# LcsNodes-Extension-Servo-Board-32-S-B_01.net
KiCad netlist of a schematic drawn in EasyEDA
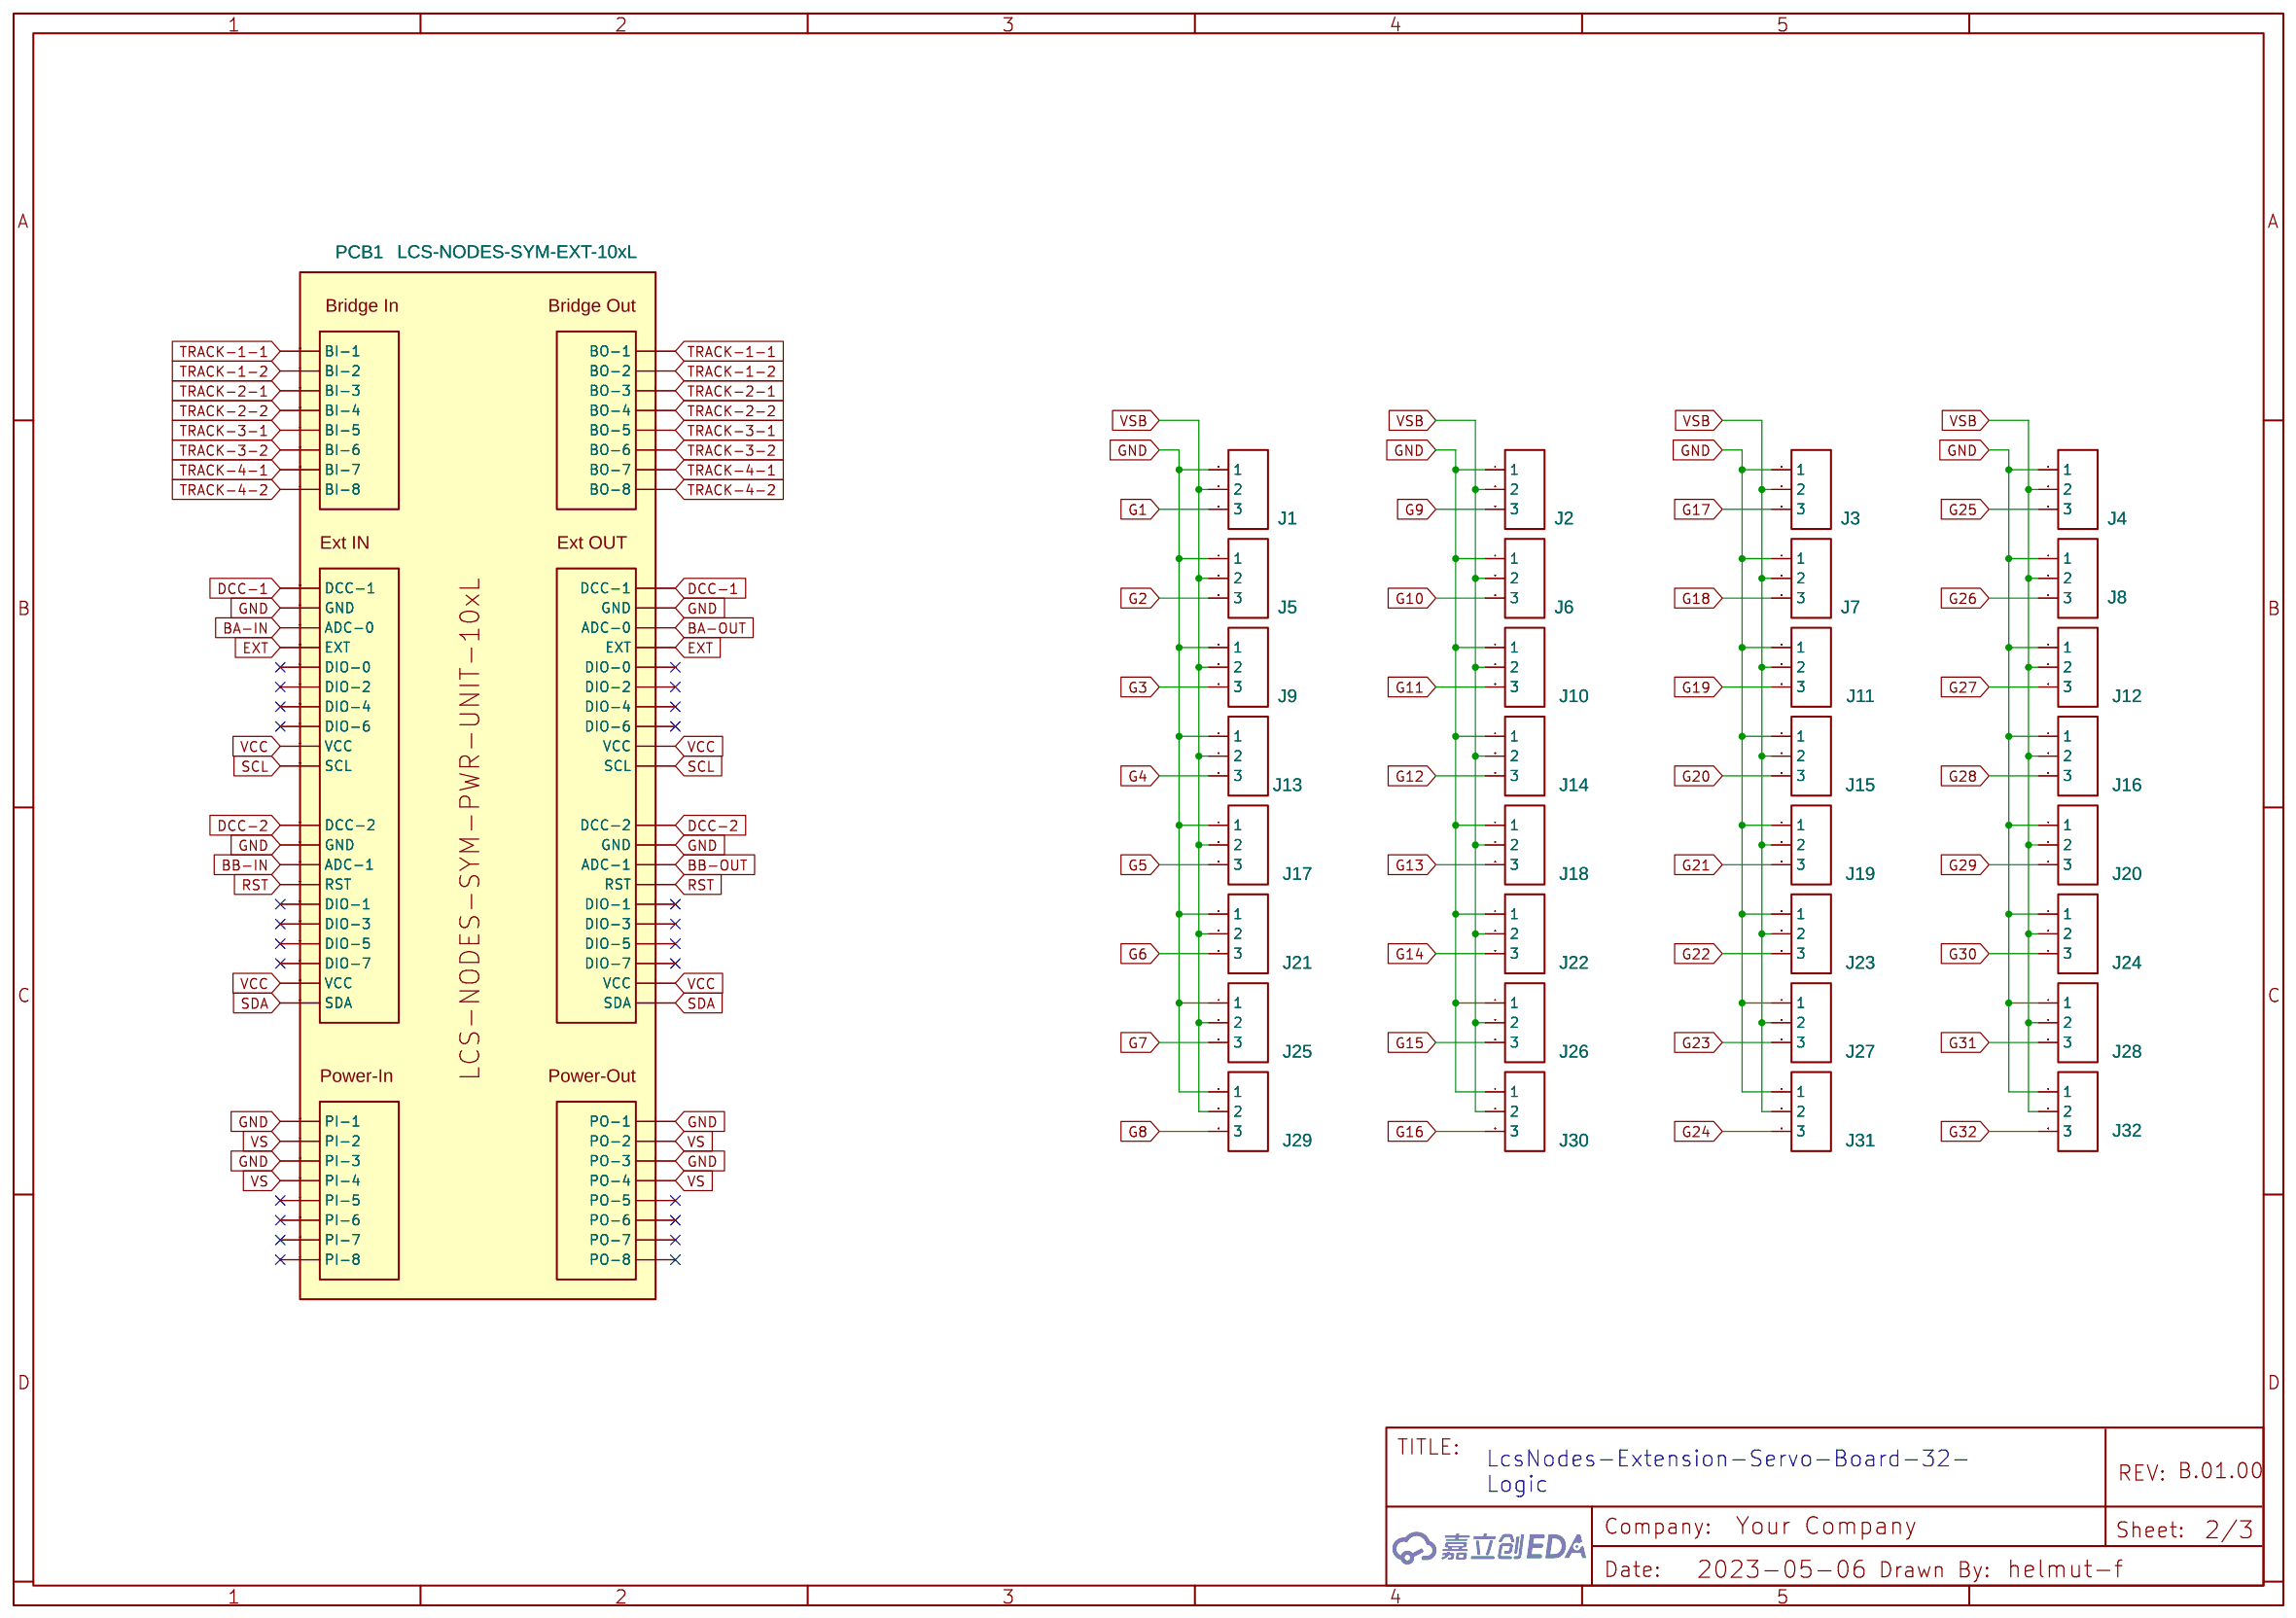
[diagram p0: Connectors]
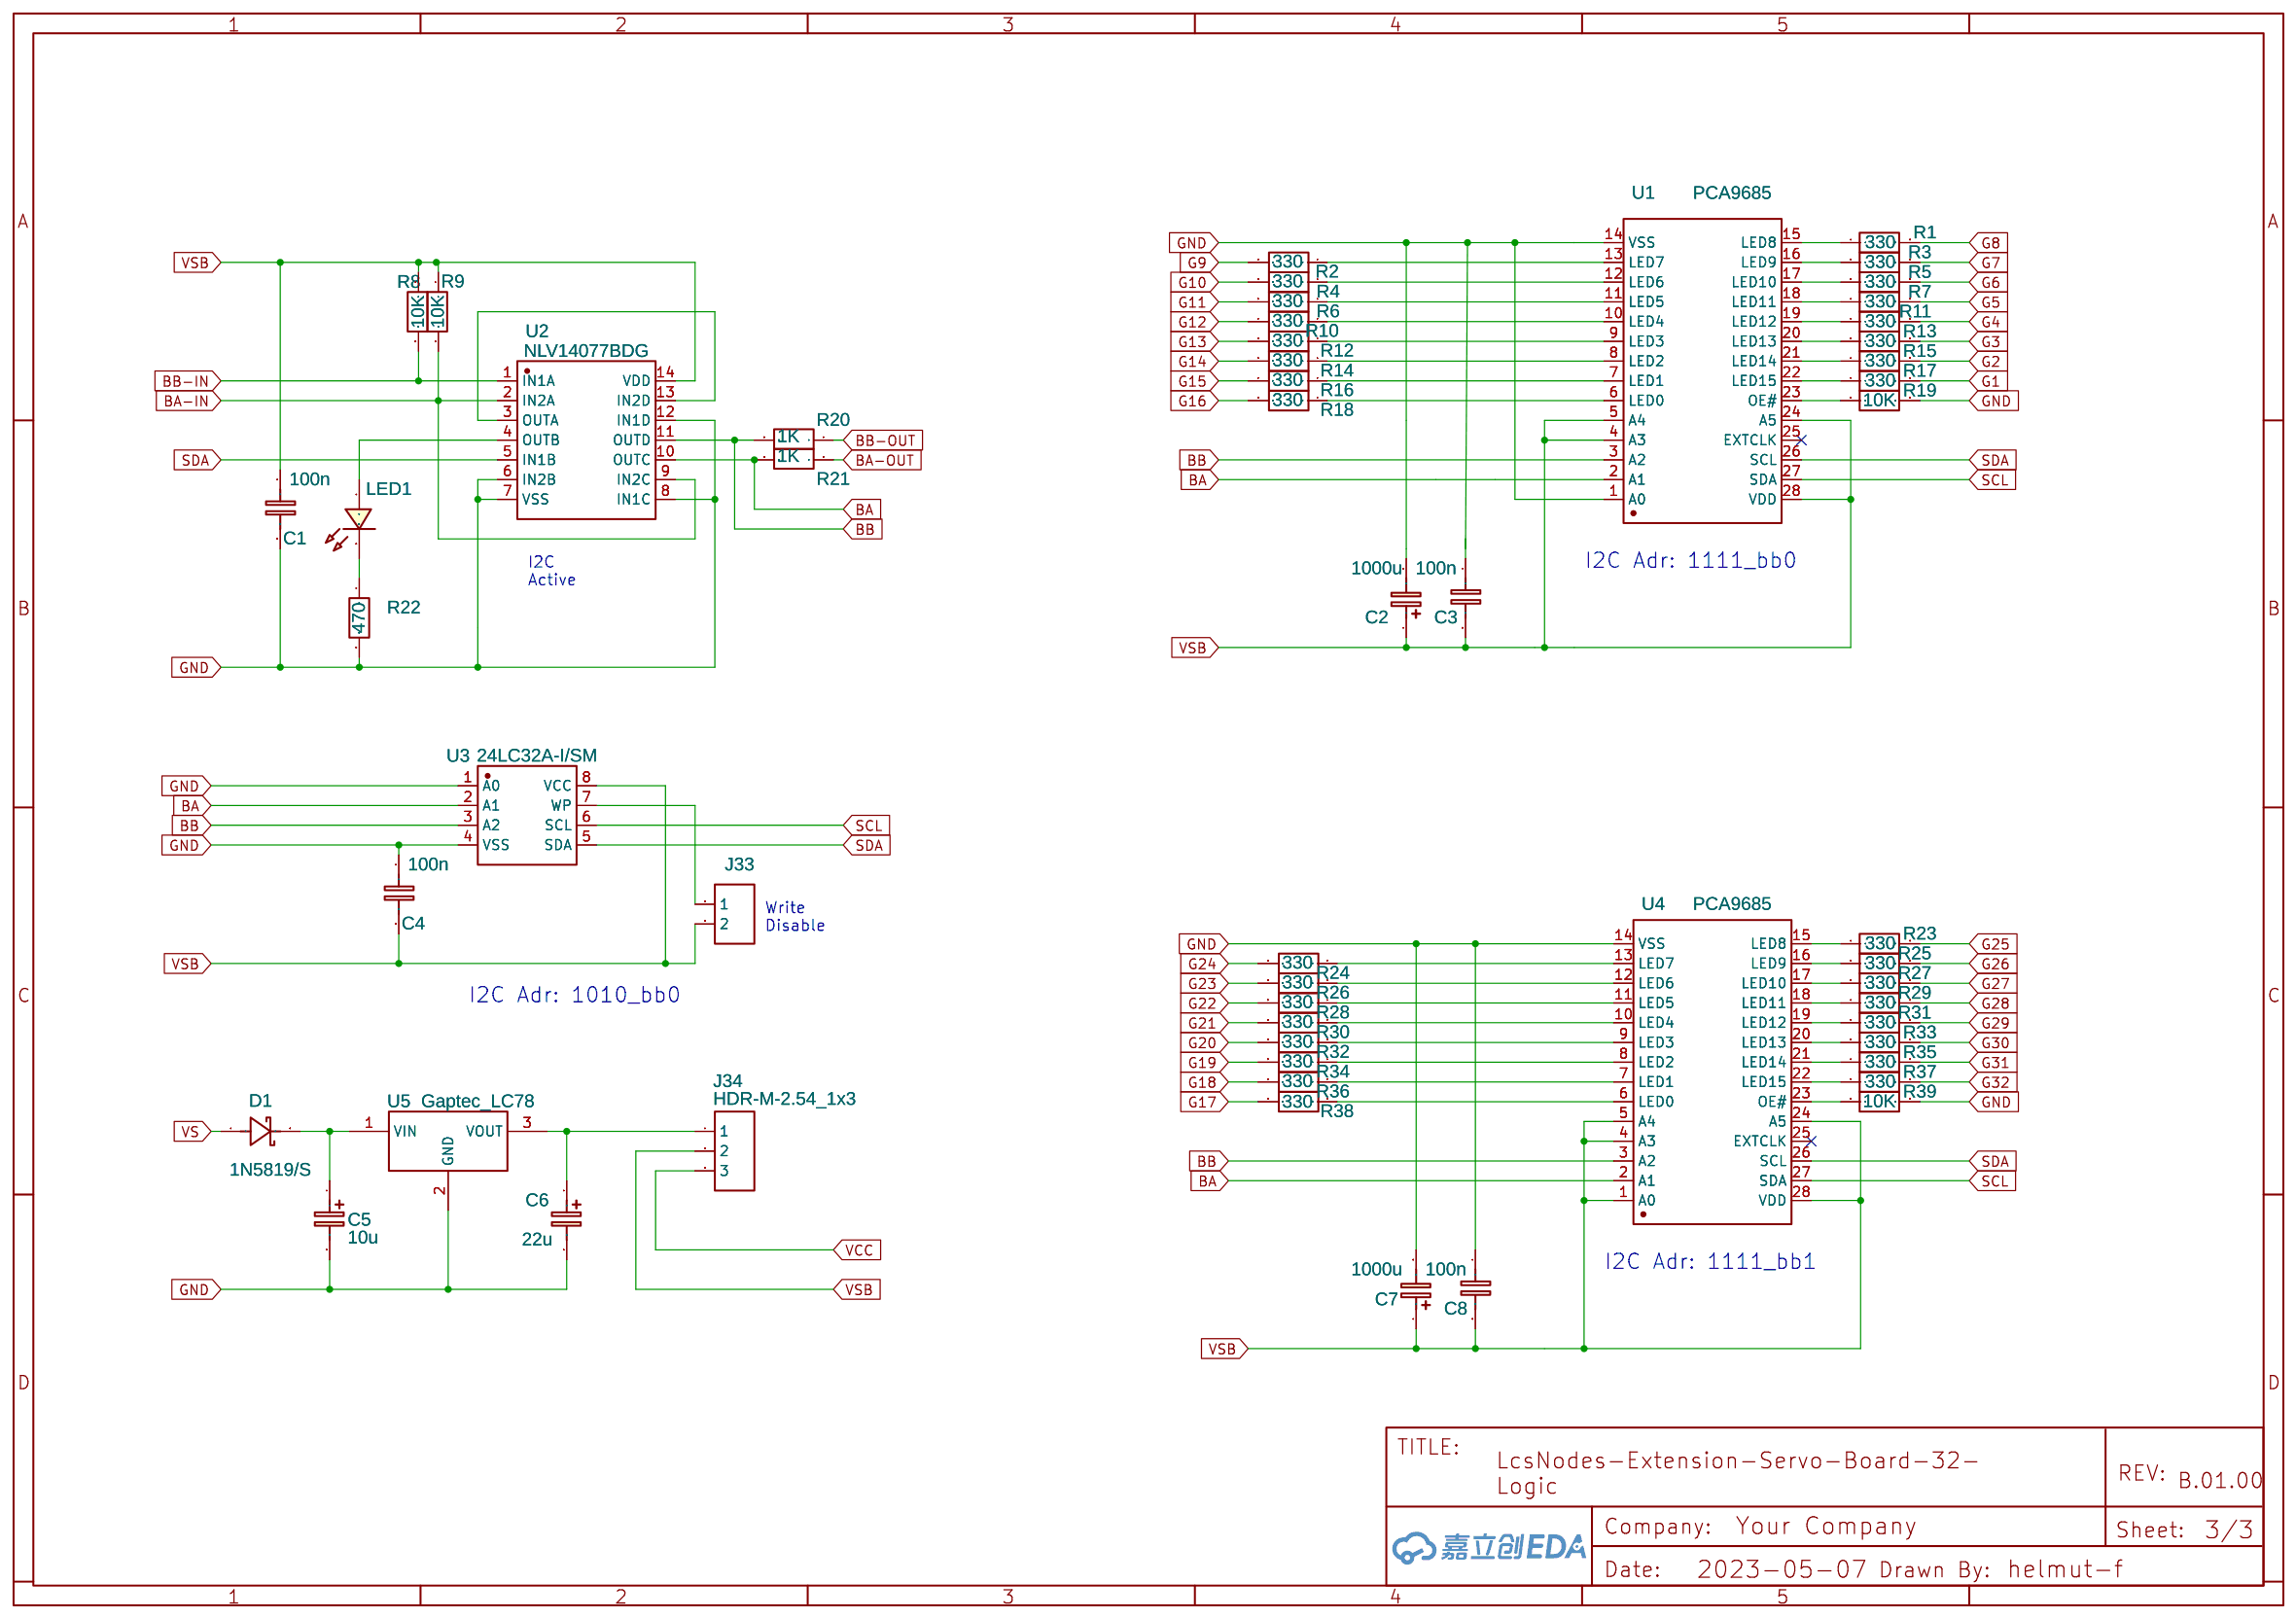
[diagram p1: Logic]
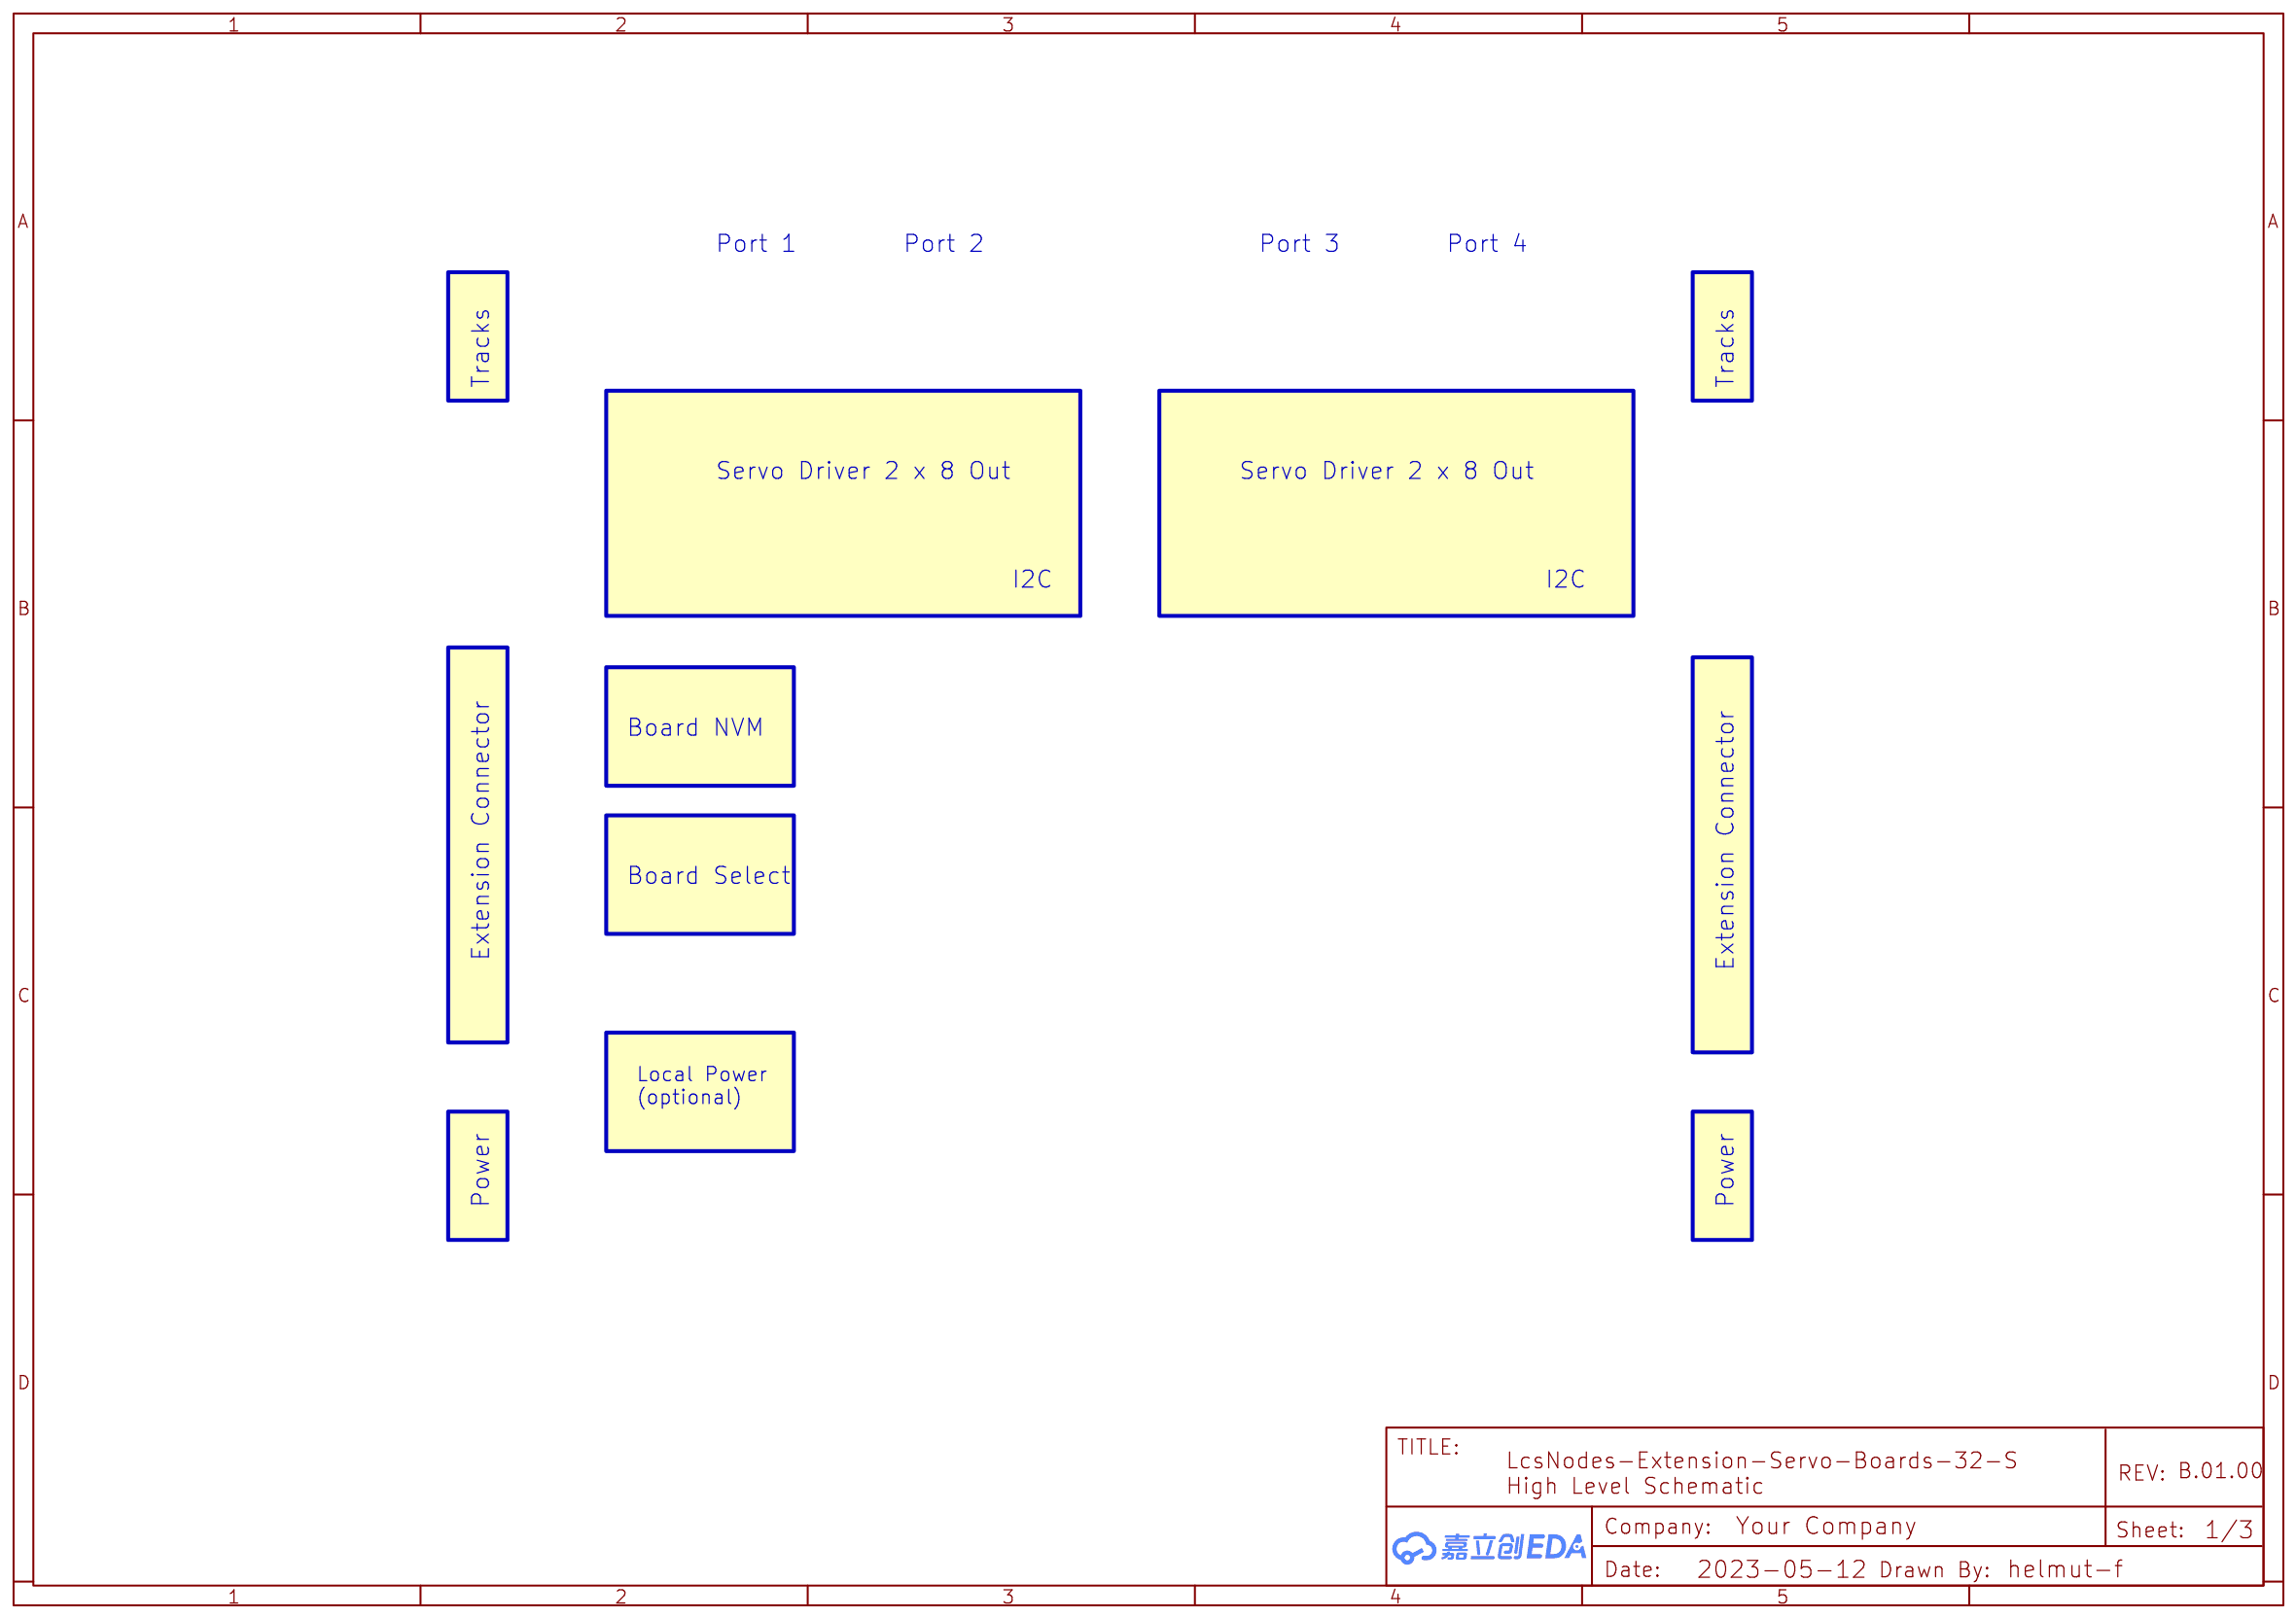
[diagram p2: High Level Schematic]

(export (version "E")
  (design (tool "Eeschema 10.0.6"))
  (components
    (comp (ref "J1") (value "HDR-M-2.54_1x3") (libsource (lib "") (part "HDR-M-2.54_1x3")))
    (comp (ref "J2") (value "HDR-M-2.54_1x3") (libsource (lib "") (part "HDR-M-2.54_1x3")))
    (comp (ref "J3") (value "HDR-M-2.54_1x3") (libsource (lib "") (part "HDR-M-2.54_1x3")))
    (comp (ref "J4") (value "HDR-M-2.54_1x3") (libsource (lib "") (part "HDR-M-2.54_1x3")))
    (comp (ref "J5") (value "HDR-M-2.54_1x3") (libsource (lib "") (part "HDR-M-2.54_1x3")))
    (comp (ref "J6") (value "HDR-M-2.54_1x3") (libsource (lib "") (part "HDR-M-2.54_1x3")))
    (comp (ref "J7") (value "HDR-M-2.54_1x3") (libsource (lib "") (part "HDR-M-2.54_1x3")))
    (comp (ref "J8") (value "HDR-M-2.54_1x3") (libsource (lib "") (part "HDR-M-2.54_1x3")))
    (comp (ref "J9") (value "HDR-M-2.54_1x3") (libsource (lib "") (part "HDR-M-2.54_1x3")))
    (comp (ref "J10") (value "HDR-M-2.54_1x3") (libsource (lib "") (part "HDR-M-2.54_1x3")))
    (comp (ref "J11") (value "HDR-M-2.54_1x3") (libsource (lib "") (part "HDR-M-2.54_1x3")))
    (comp (ref "J12") (value "HDR-M-2.54_1x3") (libsource (lib "") (part "HDR-M-2.54_1x3")))
    (comp (ref "J13") (value "HDR-M-2.54_1x3") (libsource (lib "") (part "HDR-M-2.54_1x3")))
    (comp (ref "J14") (value "HDR-M-2.54_1x3") (libsource (lib "") (part "HDR-M-2.54_1x3")))
    (comp (ref "J15") (value "HDR-M-2.54_1x3") (libsource (lib "") (part "HDR-M-2.54_1x3")))
    (comp (ref "J16") (value "HDR-M-2.54_1x3") (libsource (lib "") (part "HDR-M-2.54_1x3")))
    (comp (ref "J17") (value "HDR-M-2.54_1x3") (libsource (lib "") (part "HDR-M-2.54_1x3")))
    (comp (ref "J18") (value "HDR-M-2.54_1x3") (libsource (lib "") (part "HDR-M-2.54_1x3")))
    (comp (ref "J19") (value "HDR-M-2.54_1x3") (libsource (lib "") (part "HDR-M-2.54_1x3")))
    (comp (ref "J20") (value "HDR-M-2.54_1x3") (libsource (lib "") (part "HDR-M-2.54_1x3")))
    (comp (ref "J21") (value "HDR-M-2.54_1x3") (libsource (lib "") (part "HDR-M-2.54_1x3")))
    (comp (ref "J22") (value "HDR-M-2.54_1x3") (libsource (lib "") (part "HDR-M-2.54_1x3")))
    (comp (ref "J23") (value "HDR-M-2.54_1x3") (libsource (lib "") (part "HDR-M-2.54_1x3")))
    (comp (ref "J24") (value "HDR-M-2.54_1x3") (libsource (lib "") (part "HDR-M-2.54_1x3")))
    (comp (ref "J25") (value "HDR-M-2.54_1x3") (libsource (lib "") (part "HDR-M-2.54_1x3")))
    (comp (ref "J26") (value "HDR-M-2.54_1x3") (libsource (lib "") (part "HDR-M-2.54_1x3")))
    (comp (ref "J27") (value "HDR-M-2.54_1x3") (libsource (lib "") (part "HDR-M-2.54_1x3")))
    (comp (ref "J28") (value "HDR-M-2.54_1x3") (libsource (lib "") (part "HDR-M-2.54_1x3")))
    (comp (ref "J29") (value "HDR-M-2.54_1x3") (libsource (lib "") (part "HDR-M-2.54_1x3")))
    (comp (ref "J30") (value "HDR-M-2.54_1x3") (libsource (lib "") (part "HDR-M-2.54_1x3")))
    (comp (ref "J31") (value "HDR-M-2.54_1x3") (libsource (lib "") (part "HDR-M-2.54_1x3")))
    (comp (ref "J32") (value "HDR-M-2.54_1x3") (libsource (lib "") (part "HDR-M-2.54_1x3")))
    (comp (ref "PCB1") (value "LCS-NODES-SYM-EXT-10xL") (libsource (lib "") (part "LCS-NODES-SYM-EXT-10xL")))
    (comp (ref "C1") (value "100n") (libsource (lib "") (part "C_0603_EU_2")))
    (comp (ref "C2") (value "1000u") (libsource (lib "") (part "CE_TH_D4.0×F1.5_EU_1")))
    (comp (ref "C3") (value "100n") (libsource (lib "") (part "C_0603_EU_3")))
    (comp (ref "C4") (value "100n") (libsource (lib "") (part "C_0603_EU")))
    (comp (ref "C5") (value "10u") (libsource (lib "") (part "CE_SMD_D5.0×H5.5_EU_1")))
    (comp (ref "C6") (value "22u") (libsource (lib "") (part "CE_SMD_D5.0×H5.5_EU")))
    (comp (ref "C7") (value "1000u") (libsource (lib "") (part "CE_TH_D4.0×F1.5_EU")))
    (comp (ref "C8") (value "100n") (libsource (lib "") (part "C_0603_EU_1")))
    (comp (ref "D1") (value "1N5819/S") (libsource (lib "") (part "1N5819/S")))
    (comp (ref "J33") (value "HDR-M-2.54_1x2") (libsource (lib "") (part "HDR-M-2.54_1x2")))
    (comp (ref "J34") (value "HDR-M-2.54_1x3") (libsource (lib "") (part "HDR-M-2.54_1x3")))
    (comp (ref "LED1")
      (value "LED-0805_G")
      (fields (field (name "Manufacturer Part") "NCD0805G1") (field (name "Manufacturer") "国星光电"))
      (libsource (lib "") (part "LED-0805_G"))
    )
    (comp (ref "R1") (value "330") (libsource (lib "") (part "R_AXIAL-0.3_EU")))
    (comp (ref "R2") (value "330") (libsource (lib "") (part "R_AXIAL-0.3_EU_1")))
    (comp (ref "R3") (value "330") (libsource (lib "") (part "R_AXIAL-0.3_EU")))
    (comp (ref "R4") (value "330") (libsource (lib "") (part "R_AXIAL-0.3_EU_1")))
    (comp (ref "R5") (value "330") (libsource (lib "") (part "R_AXIAL-0.3_EU")))
    (comp (ref "R6") (value "330") (libsource (lib "") (part "R_AXIAL-0.3_EU_1")))
    (comp (ref "R7") (value "330") (libsource (lib "") (part "R_AXIAL-0.3_EU")))
    (comp (ref "R8") (value "10K") (libsource (lib "") (part "R_AXIAL-0.3_EU_3")))
    (comp (ref "R9") (value "10K") (libsource (lib "") (part "R_AXIAL-0.3_EU_3")))
    (comp (ref "R10") (value "330") (libsource (lib "") (part "R_AXIAL-0.3_EU_1")))
    (comp (ref "R11") (value "330") (libsource (lib "") (part "R_AXIAL-0.3_EU")))
    (comp (ref "R12") (value "330") (libsource (lib "") (part "R_AXIAL-0.3_EU_1")))
    (comp (ref "R13") (value "330") (libsource (lib "") (part "R_AXIAL-0.3_EU")))
    (comp (ref "R14") (value "330") (libsource (lib "") (part "R_AXIAL-0.3_EU_1")))
    (comp (ref "R15") (value "330") (libsource (lib "") (part "R_AXIAL-0.3_EU")))
    (comp (ref "R16") (value "330") (libsource (lib "") (part "R_AXIAL-0.3_EU_1")))
    (comp (ref "R17") (value "330") (libsource (lib "") (part "R_AXIAL-0.3_EU")))
    (comp (ref "R18") (value "330") (libsource (lib "") (part "R_AXIAL-0.3_EU_1")))
    (comp (ref "R19") (value "10K") (libsource (lib "") (part "R_AXIAL-0.3_EU")))
    (comp (ref "R20") (value "1K") (libsource (lib "") (part "R_AXIAL-0.3_EU_2")))
    (comp (ref "R21") (value "1K") (libsource (lib "") (part "R_AXIAL-0.3_EU_2")))
    (comp (ref "R22") (value "470") (libsource (lib "") (part "R_0805_EU")))
    (comp (ref "R23") (value "330") (libsource (lib "") (part "R_AXIAL-0.3_EU")))
    (comp (ref "R24") (value "330") (libsource (lib "") (part "R_AXIAL-0.3_EU_1")))
    (comp (ref "R25") (value "330") (libsource (lib "") (part "R_AXIAL-0.3_EU")))
    (comp (ref "R26") (value "330") (libsource (lib "") (part "R_AXIAL-0.3_EU_1")))
    (comp (ref "R27") (value "330") (libsource (lib "") (part "R_AXIAL-0.3_EU")))
    (comp (ref "R28") (value "330") (libsource (lib "") (part "R_AXIAL-0.3_EU_1")))
    (comp (ref "R29") (value "330") (libsource (lib "") (part "R_AXIAL-0.3_EU")))
    (comp (ref "R30") (value "330") (libsource (lib "") (part "R_AXIAL-0.3_EU_1")))
    (comp (ref "R31") (value "330") (libsource (lib "") (part "R_AXIAL-0.3_EU")))
    (comp (ref "R32") (value "330") (libsource (lib "") (part "R_AXIAL-0.3_EU_1")))
    (comp (ref "R33") (value "330") (libsource (lib "") (part "R_AXIAL-0.3_EU")))
    (comp (ref "R34") (value "330") (libsource (lib "") (part "R_AXIAL-0.3_EU_1")))
    (comp (ref "R35") (value "330") (libsource (lib "") (part "R_AXIAL-0.3_EU")))
    (comp (ref "R36") (value "330") (libsource (lib "") (part "R_AXIAL-0.3_EU_1")))
    (comp (ref "R37") (value "330") (libsource (lib "") (part "R_AXIAL-0.3_EU")))
    (comp (ref "R38") (value "330") (libsource (lib "") (part "R_AXIAL-0.3_EU_1")))
    (comp (ref "R39") (value "10K") (libsource (lib "") (part "R_AXIAL-0.3_EU")))
    (comp (ref "U1")
      (value "PCA9685")
      (fields (field (name "Manufacturer Part") "PCA9685PW/Q900,118") (field (name "Manufacturer") "NXP"))
      (libsource (lib "") (part "PCA9685PW/Q900,118"))
    )
    (comp (ref "U2")
      (value "NLV14077BDG")
      (fields (field (name "Manufacturer") "onsemi(安森美)"))
      (libsource (lib "") (part "NLV14077BDG"))
    )
    (comp (ref "U3")
      (value "24LC32A-I/SM")
      (fields (field (name "Manufacturer") "MICROCHIP(美国微芯)"))
      (libsource (lib "") (part "24LC32A-I/SM"))
    )
    (comp (ref "U4")
      (value "PCA9685")
      (fields (field (name "Manufacturer Part") "PCA9685PW/Q900,118") (field (name "Manufacturer") "NXP"))
      (libsource (lib "") (part "PCA9685PW/Q900,118"))
    )
    (comp (ref "U5") (value "Gaptec_LC78") (libsource (lib "") (part "Gaptec_LC78")))
  )
  (nets
    (net (code "1") (name "BA") (class "Default")
      (node (ref "R21") (pin "2") (pinfunction "2_2") (pintype "unspecified"))
      (node (ref "U1") (pin "2") (pinfunction "A1_2") (pintype "unspecified"))
      (node (ref "U2") (pin "10") (pinfunction "OUTC_10") (pintype "unspecified"))
      (node (ref "U3") (pin "2") (pinfunction "A1_2") (pintype "unspecified"))
      (node (ref "U4") (pin "2") (pinfunction "A1_2") (pintype "unspecified"))
    )
    (net (code "2") (name "BA-IN") (class "Default")
      (node (ref "PCB1") (pin "22") (pinfunction "ADC-0_22") (pintype "unspecified"))
      (node (ref "R9") (pin "2") (pinfunction "2_2") (pintype "unspecified"))
      (node (ref "U2") (pin "2") (pinfunction "IN2A_2") (pintype "unspecified"))
      (node (ref "U2") (pin "9") (pinfunction "IN2C_9") (pintype "unspecified"))
    )
    (net (code "3") (name "BA-OUT") (class "Default")
      (node (ref "PCB1") (pin "62") (pinfunction "ADC-0_62") (pintype "unspecified"))
      (node (ref "R21") (pin "1") (pinfunction "1_1") (pintype "unspecified"))
    )
    (net (code "4") (name "BB") (class "Default")
      (node (ref "R20") (pin "2") (pinfunction "2_2") (pintype "unspecified"))
      (node (ref "U1") (pin "3") (pinfunction "A2_3") (pintype "unspecified"))
      (node (ref "U2") (pin "11") (pinfunction "OUTD_11") (pintype "unspecified"))
      (node (ref "U3") (pin "3") (pinfunction "A2_3") (pintype "unspecified"))
      (node (ref "U4") (pin "3") (pinfunction "A2_3") (pintype "unspecified"))
    )
    (net (code "5") (name "BB-IN") (class "Default")
      (node (ref "PCB1") (pin "32") (pinfunction "ADC-1_32") (pintype "unspecified"))
      (node (ref "R8") (pin "2") (pinfunction "2_2") (pintype "unspecified"))
      (node (ref "U2") (pin "1") (pinfunction "IN1A_1") (pintype "unspecified"))
    )
    (net (code "6") (name "BB-OUT") (class "Default")
      (node (ref "PCB1") (pin "72") (pinfunction "ADC-1_72") (pintype "unspecified"))
      (node (ref "R20") (pin "1") (pinfunction "1_1") (pintype "unspecified"))
    )
    (net (code "7") (name "DCC-1") (class "Default")
      (node (ref "PCB1") (pin "20") (pinfunction "DCC-1_20") (pintype "unspecified"))
      (node (ref "PCB1") (pin "60") (pinfunction "DCC-1_60") (pintype "unspecified"))
    )
    (net (code "8") (name "DCC-2") (class "Default")
      (node (ref "PCB1") (pin "30") (pinfunction "DCC-2_30") (pintype "unspecified"))
      (node (ref "PCB1") (pin "70") (pinfunction "DCC-2_70") (pintype "unspecified"))
    )
    (net (code "9") (name "EXT") (class "Default")
      (node (ref "PCB1") (pin "23") (pinfunction "EXT_23") (pintype "unspecified"))
      (node (ref "PCB1") (pin "63") (pinfunction "EXT_63") (pintype "unspecified"))
    )
    (net (code "10") (name "G1") (class "Default")
      (node (ref "J1") (pin "3") (pinfunction "3_3") (pintype "input"))
      (node (ref "R17") (pin "2") (pinfunction "2_2") (pintype "unspecified"))
    )
    (net (code "11") (name "G2") (class "Default")
      (node (ref "J5") (pin "3") (pinfunction "3_3") (pintype "input"))
      (node (ref "R15") (pin "2") (pinfunction "2_2") (pintype "unspecified"))
    )
    (net (code "12") (name "G3") (class "Default")
      (node (ref "J9") (pin "3") (pinfunction "3_3") (pintype "input"))
      (node (ref "R13") (pin "2") (pinfunction "2_2") (pintype "unspecified"))
    )
    (net (code "13") (name "G4") (class "Default")
      (node (ref "J13") (pin "3") (pinfunction "3_3") (pintype "input"))
      (node (ref "R11") (pin "2") (pinfunction "2_2") (pintype "unspecified"))
    )
    (net (code "14") (name "G5") (class "Default")
      (node (ref "J17") (pin "3") (pinfunction "3_3") (pintype "input"))
      (node (ref "R7") (pin "2") (pinfunction "2_2") (pintype "unspecified"))
    )
    (net (code "15") (name "G6") (class "Default")
      (node (ref "J21") (pin "3") (pinfunction "3_3") (pintype "input"))
      (node (ref "R5") (pin "2") (pinfunction "2_2") (pintype "unspecified"))
    )
    (net (code "16") (name "G7") (class "Default")
      (node (ref "J25") (pin "3") (pinfunction "3_3") (pintype "input"))
      (node (ref "R3") (pin "2") (pinfunction "2_2") (pintype "unspecified"))
    )
    (net (code "17") (name "G8") (class "Default")
      (node (ref "J29") (pin "3") (pinfunction "3_3") (pintype "input"))
      (node (ref "R1") (pin "2") (pinfunction "2_2") (pintype "unspecified"))
    )
    (net (code "18") (name "G9") (class "Default")
      (node (ref "J2") (pin "3") (pinfunction "3_3") (pintype "input"))
      (node (ref "R2") (pin "2") (pinfunction "2_2") (pintype "unspecified"))
    )
    (net (code "19") (name "G10") (class "Default")
      (node (ref "J6") (pin "3") (pinfunction "3_3") (pintype "input"))
      (node (ref "R4") (pin "2") (pinfunction "2_2") (pintype "unspecified"))
    )
    (net (code "20") (name "G11") (class "Default")
      (node (ref "J10") (pin "3") (pinfunction "3_3") (pintype "input"))
      (node (ref "R6") (pin "2") (pinfunction "2_2") (pintype "unspecified"))
    )
    (net (code "21") (name "G12") (class "Default")
      (node (ref "J14") (pin "3") (pinfunction "3_3") (pintype "input"))
      (node (ref "R10") (pin "2") (pinfunction "2_2") (pintype "unspecified"))
    )
    (net (code "22") (name "G13") (class "Default")
      (node (ref "J18") (pin "3") (pinfunction "3_3") (pintype "input"))
      (node (ref "R12") (pin "2") (pinfunction "2_2") (pintype "unspecified"))
    )
    (net (code "23") (name "G14") (class "Default")
      (node (ref "J22") (pin "3") (pinfunction "3_3") (pintype "input"))
      (node (ref "R14") (pin "2") (pinfunction "2_2") (pintype "unspecified"))
    )
    (net (code "24") (name "G15") (class "Default")
      (node (ref "J26") (pin "3") (pinfunction "3_3") (pintype "input"))
      (node (ref "R16") (pin "2") (pinfunction "2_2") (pintype "unspecified"))
    )
    (net (code "25") (name "G16") (class "Default")
      (node (ref "J30") (pin "3") (pinfunction "3_3") (pintype "input"))
      (node (ref "R18") (pin "2") (pinfunction "2_2") (pintype "unspecified"))
    )
    (net (code "26") (name "G17") (class "Default")
      (node (ref "J3") (pin "3") (pinfunction "3_3") (pintype "input"))
      (node (ref "R38") (pin "2") (pinfunction "2_2") (pintype "unspecified"))
    )
    (net (code "27") (name "G18") (class "Default")
      (node (ref "J7") (pin "3") (pinfunction "3_3") (pintype "input"))
      (node (ref "R36") (pin "2") (pinfunction "2_2") (pintype "unspecified"))
    )
    (net (code "28") (name "G19") (class "Default")
      (node (ref "J11") (pin "3") (pinfunction "3_3") (pintype "input"))
      (node (ref "R34") (pin "2") (pinfunction "2_2") (pintype "unspecified"))
    )
    (net (code "29") (name "G20") (class "Default")
      (node (ref "J15") (pin "3") (pinfunction "3_3") (pintype "input"))
      (node (ref "R32") (pin "2") (pinfunction "2_2") (pintype "unspecified"))
    )
    (net (code "30") (name "G21") (class "Default")
      (node (ref "J19") (pin "3") (pinfunction "3_3") (pintype "input"))
      (node (ref "R30") (pin "2") (pinfunction "2_2") (pintype "unspecified"))
    )
    (net (code "31") (name "G22") (class "Default")
      (node (ref "J23") (pin "3") (pinfunction "3_3") (pintype "input"))
      (node (ref "R28") (pin "2") (pinfunction "2_2") (pintype "unspecified"))
    )
    (net (code "32") (name "G23") (class "Default")
      (node (ref "J27") (pin "3") (pinfunction "3_3") (pintype "input"))
      (node (ref "R26") (pin "2") (pinfunction "2_2") (pintype "unspecified"))
    )
    (net (code "33") (name "G24") (class "Default")
      (node (ref "J31") (pin "3") (pinfunction "3_3") (pintype "input"))
      (node (ref "R24") (pin "2") (pinfunction "2_2") (pintype "unspecified"))
    )
    (net (code "34") (name "G25") (class "Default")
      (node (ref "J4") (pin "3") (pinfunction "3_3") (pintype "input"))
      (node (ref "R23") (pin "2") (pinfunction "2_2") (pintype "unspecified"))
    )
    (net (code "35") (name "G26") (class "Default")
      (node (ref "J8") (pin "3") (pinfunction "3_3") (pintype "input"))
      (node (ref "R25") (pin "2") (pinfunction "2_2") (pintype "unspecified"))
    )
    (net (code "36") (name "G27") (class "Default")
      (node (ref "J12") (pin "3") (pinfunction "3_3") (pintype "input"))
      (node (ref "R27") (pin "2") (pinfunction "2_2") (pintype "unspecified"))
    )
    (net (code "37") (name "G28") (class "Default")
      (node (ref "J16") (pin "3") (pinfunction "3_3") (pintype "input"))
      (node (ref "R29") (pin "2") (pinfunction "2_2") (pintype "unspecified"))
    )
    (net (code "38") (name "G29") (class "Default")
      (node (ref "J20") (pin "3") (pinfunction "3_3") (pintype "input"))
      (node (ref "R31") (pin "2") (pinfunction "2_2") (pintype "unspecified"))
    )
    (net (code "39") (name "G30") (class "Default")
      (node (ref "J24") (pin "3") (pinfunction "3_3") (pintype "input"))
      (node (ref "R33") (pin "2") (pinfunction "2_2") (pintype "unspecified"))
    )
    (net (code "40") (name "G31") (class "Default")
      (node (ref "J28") (pin "3") (pinfunction "3_3") (pintype "input"))
      (node (ref "R35") (pin "2") (pinfunction "2_2") (pintype "unspecified"))
    )
    (net (code "41") (name "G32") (class "Default")
      (node (ref "J32") (pin "3") (pinfunction "3_3") (pintype "input"))
      (node (ref "R37") (pin "2") (pinfunction "2_2") (pintype "unspecified"))
    )
    (net (code "42") (name "GND") (class "Default")
      (node (ref "C1") (pin "2") (pinfunction "2_2") (pintype "unspecified"))
      (node (ref "C2") (pin "2") (pinfunction "2_2") (pintype "unspecified"))
      (node (ref "C3") (pin "1") (pinfunction "1_1") (pintype "unspecified"))
      (node (ref "C4") (pin "1") (pinfunction "1_1") (pintype "unspecified"))
      (node (ref "C5") (pin "2") (pinfunction "2_2") (pintype "unspecified"))
      (node (ref "C6") (pin "2") (pinfunction "2_2") (pintype "unspecified"))
      (node (ref "C7") (pin "2") (pinfunction "2_2") (pintype "unspecified"))
      (node (ref "C8") (pin "1") (pinfunction "1_1") (pintype "unspecified"))
      (node (ref "J1") (pin "1") (pinfunction "1_1") (pintype "input"))
      (node (ref "J10") (pin "1") (pinfunction "1_1") (pintype "input"))
      (node (ref "J11") (pin "1") (pinfunction "1_1") (pintype "input"))
      (node (ref "J12") (pin "1") (pinfunction "1_1") (pintype "input"))
      (node (ref "J13") (pin "1") (pinfunction "1_1") (pintype "input"))
      (node (ref "J14") (pin "1") (pinfunction "1_1") (pintype "input"))
      (node (ref "J15") (pin "1") (pinfunction "1_1") (pintype "input"))
      (node (ref "J16") (pin "1") (pinfunction "1_1") (pintype "input"))
      (node (ref "J17") (pin "1") (pinfunction "1_1") (pintype "input"))
      (node (ref "J18") (pin "1") (pinfunction "1_1") (pintype "input"))
      (node (ref "J19") (pin "1") (pinfunction "1_1") (pintype "input"))
      (node (ref "J2") (pin "1") (pinfunction "1_1") (pintype "input"))
      (node (ref "J20") (pin "1") (pinfunction "1_1") (pintype "input"))
      (node (ref "J21") (pin "1") (pinfunction "1_1") (pintype "input"))
      (node (ref "J22") (pin "1") (pinfunction "1_1") (pintype "input"))
      (node (ref "J23") (pin "1") (pinfunction "1_1") (pintype "input"))
      (node (ref "J24") (pin "1") (pinfunction "1_1") (pintype "input"))
      (node (ref "J25") (pin "1") (pinfunction "1_1") (pintype "input"))
      (node (ref "J26") (pin "1") (pinfunction "1_1") (pintype "input"))
      (node (ref "J27") (pin "1") (pinfunction "1_1") (pintype "input"))
      (node (ref "J28") (pin "1") (pinfunction "1_1") (pintype "input"))
      (node (ref "J29") (pin "1") (pinfunction "1_1") (pintype "input"))
      (node (ref "J3") (pin "1") (pinfunction "1_1") (pintype "input"))
      (node (ref "J30") (pin "1") (pinfunction "1_1") (pintype "input"))
      (node (ref "J31") (pin "1") (pinfunction "1_1") (pintype "input"))
      (node (ref "J32") (pin "1") (pinfunction "1_1") (pintype "input"))
      (node (ref "J4") (pin "1") (pinfunction "1_1") (pintype "input"))
      (node (ref "J5") (pin "1") (pinfunction "1_1") (pintype "input"))
      (node (ref "J6") (pin "1") (pinfunction "1_1") (pintype "input"))
      (node (ref "J7") (pin "1") (pinfunction "1_1") (pintype "input"))
      (node (ref "J8") (pin "1") (pinfunction "1_1") (pintype "input"))
      (node (ref "J9") (pin "1") (pinfunction "1_1") (pintype "input"))
      (node (ref "PCB1") (pin "21") (pinfunction "GND_21") (pintype "unspecified"))
      (node (ref "PCB1") (pin "31") (pinfunction "GND_31") (pintype "unspecified"))
      (node (ref "PCB1") (pin "40") (pinfunction "PI-1_40") (pintype "unspecified"))
      (node (ref "PCB1") (pin "42") (pinfunction "PI-3_42") (pintype "unspecified"))
      (node (ref "PCB1") (pin "61") (pinfunction "GND_61") (pintype "unspecified"))
      (node (ref "PCB1") (pin "71") (pinfunction "GND_71") (pintype "unspecified"))
      (node (ref "PCB1") (pin "80") (pinfunction "PO-1_80") (pintype "unspecified"))
      (node (ref "PCB1") (pin "82") (pinfunction "PO-3_82") (pintype "unspecified"))
      (node (ref "R19") (pin "2") (pinfunction "2_2") (pintype "unspecified"))
      (node (ref "R22") (pin "2") (pinfunction "2_2") (pintype "unspecified"))
      (node (ref "R39") (pin "2") (pinfunction "2_2") (pintype "unspecified"))
      (node (ref "U1") (pin "1") (pinfunction "A0_1") (pintype "unspecified"))
      (node (ref "U1") (pin "14") (pinfunction "VSS_14") (pintype "unspecified"))
      (node (ref "U2") (pin "12") (pinfunction "IN1D_12") (pintype "unspecified"))
      (node (ref "U2") (pin "6") (pinfunction "IN2B_6") (pintype "unspecified"))
      (node (ref "U2") (pin "7") (pinfunction "VSS_7") (pintype "unspecified"))
      (node (ref "U2") (pin "8") (pinfunction "IN1C_8") (pintype "unspecified"))
      (node (ref "U3") (pin "1") (pinfunction "A0_1") (pintype "unspecified"))
      (node (ref "U3") (pin "4") (pinfunction "VSS_4") (pintype "unspecified"))
      (node (ref "U4") (pin "14") (pinfunction "VSS_14") (pintype "unspecified"))
      (node (ref "U5") (pin "2") (pinfunction "GND_2") (pintype "unspecified"))
    )
    (net (code "43") (name "Net-(D1-K)") (class "Default")
      (node (ref "C5") (pin "1") (pinfunction "1_1") (pintype "unspecified"))
      (node (ref "D1") (pin "2") (pinfunction "K_2") (pintype "unspecified"))
      (node (ref "U5") (pin "1") (pinfunction "VIN_1") (pintype "unspecified"))
    )
    (net (code "44") (name "Net-(LED1-Pad2)") (class "Default")
      (node (ref "LED1") (pin "2") (pinfunction "2_2") (pintype "unspecified"))
      (node (ref "R22") (pin "1") (pinfunction "1_1") (pintype "unspecified"))
    )
    (net (code "45") (name "Net-(U1-LED0)") (class "Default")
      (node (ref "R18") (pin "1") (pinfunction "1_1") (pintype "unspecified"))
      (node (ref "U1") (pin "6") (pinfunction "LED0_6") (pintype "unspecified"))
    )
    (net (code "46") (name "Net-(U1-LED1)") (class "Default")
      (node (ref "R16") (pin "1") (pinfunction "1_1") (pintype "unspecified"))
      (node (ref "U1") (pin "7") (pinfunction "LED1_7") (pintype "unspecified"))
    )
    (net (code "47") (name "Net-(U1-LED2)") (class "Default")
      (node (ref "R14") (pin "1") (pinfunction "1_1") (pintype "unspecified"))
      (node (ref "U1") (pin "8") (pinfunction "LED2_8") (pintype "unspecified"))
    )
    (net (code "48") (name "Net-(U1-LED3)") (class "Default")
      (node (ref "R12") (pin "1") (pinfunction "1_1") (pintype "unspecified"))
      (node (ref "U1") (pin "9") (pinfunction "LED3_9") (pintype "unspecified"))
    )
    (net (code "49") (name "Net-(U1-LED4)") (class "Default")
      (node (ref "R10") (pin "1") (pinfunction "1_1") (pintype "unspecified"))
      (node (ref "U1") (pin "10") (pinfunction "LED4_10") (pintype "unspecified"))
    )
    (net (code "50") (name "Net-(U1-LED5)") (class "Default")
      (node (ref "R6") (pin "1") (pinfunction "1_1") (pintype "unspecified"))
      (node (ref "U1") (pin "11") (pinfunction "LED5_11") (pintype "unspecified"))
    )
    (net (code "51") (name "Net-(U1-LED6)") (class "Default")
      (node (ref "R4") (pin "1") (pinfunction "1_1") (pintype "unspecified"))
      (node (ref "U1") (pin "12") (pinfunction "LED6_12") (pintype "unspecified"))
    )
    (net (code "52") (name "Net-(U1-LED7)") (class "Default")
      (node (ref "R2") (pin "1") (pinfunction "1_1") (pintype "unspecified"))
      (node (ref "U1") (pin "13") (pinfunction "LED7_13") (pintype "unspecified"))
    )
    (net (code "53") (name "Net-(U1-LED8)") (class "Default")
      (node (ref "R1") (pin "1") (pinfunction "1_1") (pintype "unspecified"))
      (node (ref "U1") (pin "15") (pinfunction "LED8_15") (pintype "unspecified"))
    )
    (net (code "54") (name "Net-(U1-LED9)") (class "Default")
      (node (ref "R3") (pin "1") (pinfunction "1_1") (pintype "unspecified"))
      (node (ref "U1") (pin "16") (pinfunction "LED9_16") (pintype "unspecified"))
    )
    (net (code "55") (name "Net-(U1-LED10)") (class "Default")
      (node (ref "R5") (pin "1") (pinfunction "1_1") (pintype "unspecified"))
      (node (ref "U1") (pin "17") (pinfunction "LED10_17") (pintype "unspecified"))
    )
    (net (code "56") (name "Net-(U1-LED11)") (class "Default")
      (node (ref "R7") (pin "1") (pinfunction "1_1") (pintype "unspecified"))
      (node (ref "U1") (pin "18") (pinfunction "LED11_18") (pintype "unspecified"))
    )
    (net (code "57") (name "Net-(U1-LED12)") (class "Default")
      (node (ref "R11") (pin "1") (pinfunction "1_1") (pintype "unspecified"))
      (node (ref "U1") (pin "19") (pinfunction "LED12_19") (pintype "unspecified"))
    )
    (net (code "58") (name "Net-(U1-LED13)") (class "Default")
      (node (ref "R13") (pin "1") (pinfunction "1_1") (pintype "unspecified"))
      (node (ref "U1") (pin "20") (pinfunction "LED13_20") (pintype "unspecified"))
    )
    (net (code "59") (name "Net-(U1-LED14)") (class "Default")
      (node (ref "R15") (pin "1") (pinfunction "1_1") (pintype "unspecified"))
      (node (ref "U1") (pin "21") (pinfunction "LED14_21") (pintype "unspecified"))
    )
    (net (code "60") (name "Net-(U1-LED15)") (class "Default")
      (node (ref "R17") (pin "1") (pinfunction "1_1") (pintype "unspecified"))
      (node (ref "U1") (pin "22") (pinfunction "LED15_22") (pintype "unspecified"))
    )
    (net (code "61") (name "Net-(U1-OE#)") (class "Default")
      (node (ref "R19") (pin "1") (pinfunction "1_1") (pintype "unspecified"))
      (node (ref "U1") (pin "23") (pinfunction "OE#_23") (pintype "unspecified"))
    )
    (net (code "62") (name "Net-(U2-IN2D)") (class "Default")
      (node (ref "U2") (pin "13") (pinfunction "IN2D_13") (pintype "unspecified"))
      (node (ref "U2") (pin "3") (pinfunction "OUTA_3") (pintype "unspecified"))
    )
    (net (code "63") (name "Net-(U2-OUTB)") (class "Default")
      (node (ref "LED1") (pin "1") (pinfunction "1_1") (pintype "unspecified"))
      (node (ref "U2") (pin "4") (pinfunction "OUTB_4") (pintype "unspecified"))
    )
    (net (code "64") (name "Net-(U3-WP)") (class "Default")
      (node (ref "J33") (pin "1") (pinfunction "1_1") (pintype "unspecified"))
      (node (ref "U3") (pin "7") (pinfunction "WP_7") (pintype "unspecified"))
    )
    (net (code "65") (name "Net-(U4-LED0)") (class "Default")
      (node (ref "R38") (pin "1") (pinfunction "1_1") (pintype "unspecified"))
      (node (ref "U4") (pin "6") (pinfunction "LED0_6") (pintype "unspecified"))
    )
    (net (code "66") (name "Net-(U4-LED1)") (class "Default")
      (node (ref "R36") (pin "1") (pinfunction "1_1") (pintype "unspecified"))
      (node (ref "U4") (pin "7") (pinfunction "LED1_7") (pintype "unspecified"))
    )
    (net (code "67") (name "Net-(U4-LED2)") (class "Default")
      (node (ref "R34") (pin "1") (pinfunction "1_1") (pintype "unspecified"))
      (node (ref "U4") (pin "8") (pinfunction "LED2_8") (pintype "unspecified"))
    )
    (net (code "68") (name "Net-(U4-LED3)") (class "Default")
      (node (ref "R32") (pin "1") (pinfunction "1_1") (pintype "unspecified"))
      (node (ref "U4") (pin "9") (pinfunction "LED3_9") (pintype "unspecified"))
    )
    (net (code "69") (name "Net-(U4-LED4)") (class "Default")
      (node (ref "R30") (pin "1") (pinfunction "1_1") (pintype "unspecified"))
      (node (ref "U4") (pin "10") (pinfunction "LED4_10") (pintype "unspecified"))
    )
    (net (code "70") (name "Net-(U4-LED5)") (class "Default")
      (node (ref "R28") (pin "1") (pinfunction "1_1") (pintype "unspecified"))
      (node (ref "U4") (pin "11") (pinfunction "LED5_11") (pintype "unspecified"))
    )
    (net (code "71") (name "Net-(U4-LED6)") (class "Default")
      (node (ref "R26") (pin "1") (pinfunction "1_1") (pintype "unspecified"))
      (node (ref "U4") (pin "12") (pinfunction "LED6_12") (pintype "unspecified"))
    )
    (net (code "72") (name "Net-(U4-LED7)") (class "Default")
      (node (ref "R24") (pin "1") (pinfunction "1_1") (pintype "unspecified"))
      (node (ref "U4") (pin "13") (pinfunction "LED7_13") (pintype "unspecified"))
    )
    (net (code "73") (name "Net-(U4-LED8)") (class "Default")
      (node (ref "R23") (pin "1") (pinfunction "1_1") (pintype "unspecified"))
      (node (ref "U4") (pin "15") (pinfunction "LED8_15") (pintype "unspecified"))
    )
    (net (code "74") (name "Net-(U4-LED9)") (class "Default")
      (node (ref "R25") (pin "1") (pinfunction "1_1") (pintype "unspecified"))
      (node (ref "U4") (pin "16") (pinfunction "LED9_16") (pintype "unspecified"))
    )
    (net (code "75") (name "Net-(U4-LED10)") (class "Default")
      (node (ref "R27") (pin "1") (pinfunction "1_1") (pintype "unspecified"))
      (node (ref "U4") (pin "17") (pinfunction "LED10_17") (pintype "unspecified"))
    )
    (net (code "76") (name "Net-(U4-LED11)") (class "Default")
      (node (ref "R29") (pin "1") (pinfunction "1_1") (pintype "unspecified"))
      (node (ref "U4") (pin "18") (pinfunction "LED11_18") (pintype "unspecified"))
    )
    (net (code "77") (name "Net-(U4-LED12)") (class "Default")
      (node (ref "R31") (pin "1") (pinfunction "1_1") (pintype "unspecified"))
      (node (ref "U4") (pin "19") (pinfunction "LED12_19") (pintype "unspecified"))
    )
    (net (code "78") (name "Net-(U4-LED13)") (class "Default")
      (node (ref "R33") (pin "1") (pinfunction "1_1") (pintype "unspecified"))
      (node (ref "U4") (pin "20") (pinfunction "LED13_20") (pintype "unspecified"))
    )
    (net (code "79") (name "Net-(U4-LED14)") (class "Default")
      (node (ref "R35") (pin "1") (pinfunction "1_1") (pintype "unspecified"))
      (node (ref "U4") (pin "21") (pinfunction "LED14_21") (pintype "unspecified"))
    )
    (net (code "80") (name "Net-(U4-LED15)") (class "Default")
      (node (ref "R37") (pin "1") (pinfunction "1_1") (pintype "unspecified"))
      (node (ref "U4") (pin "22") (pinfunction "LED15_22") (pintype "unspecified"))
    )
    (net (code "81") (name "Net-(U4-OE#)") (class "Default")
      (node (ref "R39") (pin "1") (pinfunction "1_1") (pintype "unspecified"))
      (node (ref "U4") (pin "23") (pinfunction "OE#_23") (pintype "unspecified"))
    )
    (net (code "82") (name "Net-(U5-VOUT)") (class "Default")
      (node (ref "C6") (pin "1") (pinfunction "1_1") (pintype "unspecified"))
      (node (ref "J34") (pin "1") (pinfunction "1_1") (pintype "input"))
      (node (ref "U5") (pin "3") (pinfunction "VOUT_3") (pintype "unspecified"))
    )
    (net (code "83") (name "RST") (class "Default")
      (node (ref "PCB1") (pin "33") (pinfunction "RST_33") (pintype "unspecified"))
      (node (ref "PCB1") (pin "73") (pinfunction "RST_73") (pintype "unspecified"))
    )
    (net (code "84") (name "SCL") (class "Default")
      (node (ref "PCB1") (pin "29") (pinfunction "SCL_29") (pintype "unspecified"))
      (node (ref "PCB1") (pin "69") (pinfunction "SCL_69") (pintype "unspecified"))
      (node (ref "U1") (pin "27") (pinfunction "SDA_27") (pintype "unspecified"))
      (node (ref "U3") (pin "6") (pinfunction "SCL_6") (pintype "unspecified"))
      (node (ref "U4") (pin "27") (pinfunction "SDA_27") (pintype "unspecified"))
    )
    (net (code "85") (name "SDA") (class "Default")
      (node (ref "PCB1") (pin "39") (pinfunction "SDA_39") (pintype "unspecified"))
      (node (ref "PCB1") (pin "79") (pinfunction "SDA_79") (pintype "unspecified"))
      (node (ref "U1") (pin "26") (pinfunction "SCL_26") (pintype "unspecified"))
      (node (ref "U2") (pin "5") (pinfunction "IN1B_5") (pintype "unspecified"))
      (node (ref "U3") (pin "5") (pinfunction "SDA_5") (pintype "unspecified"))
      (node (ref "U4") (pin "26") (pinfunction "SCL_26") (pintype "unspecified"))
    )
    (net (code "86") (name "TRACK-1-1") (class "Default")
      (node (ref "PCB1") (pin "10") (pinfunction "BI-1_10") (pintype "unspecified"))
      (node (ref "PCB1") (pin "50") (pinfunction "BO-1_50") (pintype "unspecified"))
    )
    (net (code "87") (name "TRACK-1-2") (class "Default")
      (node (ref "PCB1") (pin "11") (pinfunction "BI-2_11") (pintype "unspecified"))
      (node (ref "PCB1") (pin "51") (pinfunction "BO-2_51") (pintype "unspecified"))
    )
    (net (code "88") (name "TRACK-2-1") (class "Default")
      (node (ref "PCB1") (pin "12") (pinfunction "BI-3_12") (pintype "unspecified"))
      (node (ref "PCB1") (pin "52") (pinfunction "BO-3_52") (pintype "unspecified"))
    )
    (net (code "89") (name "TRACK-2-2") (class "Default")
      (node (ref "PCB1") (pin "13") (pinfunction "BI-4_13") (pintype "unspecified"))
      (node (ref "PCB1") (pin "53") (pinfunction "BO-4_53") (pintype "unspecified"))
    )
    (net (code "90") (name "TRACK-3-1") (class "Default")
      (node (ref "PCB1") (pin "14") (pinfunction "BI-5_14") (pintype "unspecified"))
      (node (ref "PCB1") (pin "54") (pinfunction "BO-5_54") (pintype "unspecified"))
    )
    (net (code "91") (name "TRACK-3-2") (class "Default")
      (node (ref "PCB1") (pin "15") (pinfunction "BI-6_15") (pintype "unspecified"))
      (node (ref "PCB1") (pin "55") (pinfunction "BO-6_55") (pintype "unspecified"))
    )
    (net (code "92") (name "TRACK-4-1") (class "Default")
      (node (ref "PCB1") (pin "16") (pinfunction "BI-7_16") (pintype "unspecified"))
      (node (ref "PCB1") (pin "56") (pinfunction "BO-7_56") (pintype "unspecified"))
    )
    (net (code "93") (name "TRACK-4-2") (class "Default")
      (node (ref "PCB1") (pin "17") (pinfunction "BI-8_17") (pintype "unspecified"))
      (node (ref "PCB1") (pin "57") (pinfunction "BO-8_57") (pintype "unspecified"))
    )
    (net (code "94") (name "VCC") (class "Default")
      (node (ref "J34") (pin "3") (pinfunction "3_3") (pintype "input"))
      (node (ref "PCB1") (pin "28") (pinfunction "VCC_28") (pintype "unspecified"))
      (node (ref "PCB1") (pin "38") (pinfunction "VCC_38") (pintype "unspecified"))
      (node (ref "PCB1") (pin "68") (pinfunction "VCC_68") (pintype "unspecified"))
      (node (ref "PCB1") (pin "78") (pinfunction "VCC_78") (pintype "unspecified"))
    )
    (net (code "95") (name "VS") (class "Default")
      (node (ref "D1") (pin "1") (pinfunction "A_1") (pintype "unspecified"))
      (node (ref "PCB1") (pin "41") (pinfunction "PI-2_41") (pintype "unspecified"))
      (node (ref "PCB1") (pin "43") (pinfunction "PI-4_43") (pintype "unspecified"))
      (node (ref "PCB1") (pin "81") (pinfunction "PO-2_81") (pintype "unspecified"))
      (node (ref "PCB1") (pin "83") (pinfunction "PO-4_83") (pintype "unspecified"))
    )
    (net (code "96") (name "VSB") (class "Default")
      (node (ref "C1") (pin "1") (pinfunction "1_1") (pintype "unspecified"))
      (node (ref "C2") (pin "1") (pinfunction "1_1") (pintype "unspecified"))
      (node (ref "C3") (pin "2") (pinfunction "2_2") (pintype "unspecified"))
      (node (ref "C4") (pin "2") (pinfunction "2_2") (pintype "unspecified"))
      (node (ref "C7") (pin "1") (pinfunction "1_1") (pintype "unspecified"))
      (node (ref "C8") (pin "2") (pinfunction "2_2") (pintype "unspecified"))
      (node (ref "J1") (pin "2") (pinfunction "2_2") (pintype "input"))
      (node (ref "J10") (pin "2") (pinfunction "2_2") (pintype "input"))
      (node (ref "J11") (pin "2") (pinfunction "2_2") (pintype "input"))
      (node (ref "J12") (pin "2") (pinfunction "2_2") (pintype "input"))
      (node (ref "J13") (pin "2") (pinfunction "2_2") (pintype "input"))
      (node (ref "J14") (pin "2") (pinfunction "2_2") (pintype "input"))
      (node (ref "J15") (pin "2") (pinfunction "2_2") (pintype "input"))
      (node (ref "J16") (pin "2") (pinfunction "2_2") (pintype "input"))
      (node (ref "J17") (pin "2") (pinfunction "2_2") (pintype "input"))
      (node (ref "J18") (pin "2") (pinfunction "2_2") (pintype "input"))
      (node (ref "J19") (pin "2") (pinfunction "2_2") (pintype "input"))
      (node (ref "J2") (pin "2") (pinfunction "2_2") (pintype "input"))
      (node (ref "J20") (pin "2") (pinfunction "2_2") (pintype "input"))
      (node (ref "J21") (pin "2") (pinfunction "2_2") (pintype "input"))
      (node (ref "J22") (pin "2") (pinfunction "2_2") (pintype "input"))
      (node (ref "J23") (pin "2") (pinfunction "2_2") (pintype "input"))
      (node (ref "J24") (pin "2") (pinfunction "2_2") (pintype "input"))
      (node (ref "J25") (pin "2") (pinfunction "2_2") (pintype "input"))
      (node (ref "J26") (pin "2") (pinfunction "2_2") (pintype "input"))
      (node (ref "J27") (pin "2") (pinfunction "2_2") (pintype "input"))
      (node (ref "J28") (pin "2") (pinfunction "2_2") (pintype "input"))
      (node (ref "J29") (pin "2") (pinfunction "2_2") (pintype "input"))
      (node (ref "J3") (pin "2") (pinfunction "2_2") (pintype "input"))
      (node (ref "J30") (pin "2") (pinfunction "2_2") (pintype "input"))
      (node (ref "J31") (pin "2") (pinfunction "2_2") (pintype "input"))
      (node (ref "J32") (pin "2") (pinfunction "2_2") (pintype "input"))
      (node (ref "J33") (pin "2") (pinfunction "2_2") (pintype "unspecified"))
      (node (ref "J34") (pin "2") (pinfunction "2_2") (pintype "input"))
      (node (ref "J4") (pin "2") (pinfunction "2_2") (pintype "input"))
      (node (ref "J5") (pin "2") (pinfunction "2_2") (pintype "input"))
      (node (ref "J6") (pin "2") (pinfunction "2_2") (pintype "input"))
      (node (ref "J7") (pin "2") (pinfunction "2_2") (pintype "input"))
      (node (ref "J8") (pin "2") (pinfunction "2_2") (pintype "input"))
      (node (ref "J9") (pin "2") (pinfunction "2_2") (pintype "input"))
      (node (ref "R8") (pin "1") (pinfunction "1_1") (pintype "unspecified"))
      (node (ref "R9") (pin "1") (pinfunction "1_1") (pintype "unspecified"))
      (node (ref "U1") (pin "24") (pinfunction "A5_24") (pintype "unspecified"))
      (node (ref "U1") (pin "28") (pinfunction "VDD_28") (pintype "unspecified"))
      (node (ref "U1") (pin "4") (pinfunction "A3_4") (pintype "unspecified"))
      (node (ref "U1") (pin "5") (pinfunction "A4_5") (pintype "unspecified"))
      (node (ref "U2") (pin "14") (pinfunction "VDD_14") (pintype "unspecified"))
      (node (ref "U3") (pin "8") (pinfunction "VCC_8") (pintype "unspecified"))
      (node (ref "U4") (pin "1") (pinfunction "A0_1") (pintype "unspecified"))
      (node (ref "U4") (pin "24") (pinfunction "A5_24") (pintype "unspecified"))
      (node (ref "U4") (pin "28") (pinfunction "VDD_28") (pintype "unspecified"))
      (node (ref "U4") (pin "4") (pinfunction "A3_4") (pintype "unspecified"))
      (node (ref "U4") (pin "5") (pinfunction "A4_5") (pintype "unspecified"))
    )
    (net (code "97") (name "unconnected-(PCB1-DIO-0-Pad24)") (class "Default")
      (node (ref "PCB1") (pin "24") (pinfunction "DIO-0_24") (pintype "unspecified+no_connect"))
    )
    (net (code "98") (name "unconnected-(PCB1-DIO-0-Pad64)") (class "Default")
      (node (ref "PCB1") (pin "64") (pinfunction "DIO-0_64") (pintype "unspecified+no_connect"))
    )
    (net (code "99") (name "unconnected-(PCB1-DIO-1-Pad34)") (class "Default")
      (node (ref "PCB1") (pin "34") (pinfunction "DIO-1_34") (pintype "unspecified+no_connect"))
    )
    (net (code "100") (name "unconnected-(PCB1-DIO-1-Pad74)") (class "Default")
      (node (ref "PCB1") (pin "74") (pinfunction "DIO-1_74") (pintype "unspecified+no_connect"))
    )
    (net (code "101") (name "unconnected-(PCB1-DIO-2-Pad25)") (class "Default")
      (node (ref "PCB1") (pin "25") (pinfunction "DIO-2_25") (pintype "unspecified+no_connect"))
    )
    (net (code "102") (name "unconnected-(PCB1-DIO-2-Pad65)") (class "Default")
      (node (ref "PCB1") (pin "65") (pinfunction "DIO-2_65") (pintype "unspecified+no_connect"))
    )
    (net (code "103") (name "unconnected-(PCB1-DIO-3-Pad35)") (class "Default")
      (node (ref "PCB1") (pin "35") (pinfunction "DIO-3_35") (pintype "unspecified+no_connect"))
    )
    (net (code "104") (name "unconnected-(PCB1-DIO-3-Pad75)") (class "Default")
      (node (ref "PCB1") (pin "75") (pinfunction "DIO-3_75") (pintype "unspecified+no_connect"))
    )
    (net (code "105") (name "unconnected-(PCB1-DIO-4-Pad26)") (class "Default")
      (node (ref "PCB1") (pin "26") (pinfunction "DIO-4_26") (pintype "unspecified+no_connect"))
    )
    (net (code "106") (name "unconnected-(PCB1-DIO-4-Pad66)") (class "Default")
      (node (ref "PCB1") (pin "66") (pinfunction "DIO-4_66") (pintype "unspecified+no_connect"))
    )
    (net (code "107") (name "unconnected-(PCB1-DIO-5-Pad36)") (class "Default")
      (node (ref "PCB1") (pin "36") (pinfunction "DIO-5_36") (pintype "unspecified+no_connect"))
    )
    (net (code "108") (name "unconnected-(PCB1-DIO-5-Pad76)") (class "Default")
      (node (ref "PCB1") (pin "76") (pinfunction "DIO-5_76") (pintype "unspecified+no_connect"))
    )
    (net (code "109") (name "unconnected-(PCB1-DIO-6-Pad27)") (class "Default")
      (node (ref "PCB1") (pin "27") (pinfunction "DIO-6_27") (pintype "unspecified+no_connect"))
    )
    (net (code "110") (name "unconnected-(PCB1-DIO-6-Pad67)") (class "Default")
      (node (ref "PCB1") (pin "67") (pinfunction "DIO-6_67") (pintype "unspecified+no_connect"))
    )
    (net (code "111") (name "unconnected-(PCB1-DIO-7-Pad37)") (class "Default")
      (node (ref "PCB1") (pin "37") (pinfunction "DIO-7_37") (pintype "unspecified+no_connect"))
    )
    (net (code "112") (name "unconnected-(PCB1-DIO-7-Pad77)") (class "Default")
      (node (ref "PCB1") (pin "77") (pinfunction "DIO-7_77") (pintype "unspecified+no_connect"))
    )
    (net (code "113") (name "unconnected-(PCB1-PI-5-Pad44)") (class "Default")
      (node (ref "PCB1") (pin "44") (pinfunction "PI-5_44") (pintype "unspecified+no_connect"))
    )
    (net (code "114") (name "unconnected-(PCB1-PI-6-Pad45)") (class "Default")
      (node (ref "PCB1") (pin "45") (pinfunction "PI-6_45") (pintype "unspecified+no_connect"))
    )
    (net (code "115") (name "unconnected-(PCB1-PI-7-Pad46)") (class "Default")
      (node (ref "PCB1") (pin "46") (pinfunction "PI-7_46") (pintype "unspecified+no_connect"))
    )
    (net (code "116") (name "unconnected-(PCB1-PI-8-Pad47)") (class "Default")
      (node (ref "PCB1") (pin "47") (pinfunction "PI-8_47") (pintype "unspecified+no_connect"))
    )
    (net (code "117") (name "unconnected-(PCB1-PO-5-Pad84)") (class "Default")
      (node (ref "PCB1") (pin "84") (pinfunction "PO-5_84") (pintype "unspecified+no_connect"))
    )
    (net (code "118") (name "unconnected-(PCB1-PO-6-Pad85)") (class "Default")
      (node (ref "PCB1") (pin "85") (pinfunction "PO-6_85") (pintype "unspecified+no_connect"))
    )
    (net (code "119") (name "unconnected-(PCB1-PO-7-Pad86)") (class "Default")
      (node (ref "PCB1") (pin "86") (pinfunction "PO-7_86") (pintype "unspecified+no_connect"))
    )
    (net (code "120") (name "unconnected-(PCB1-PO-8-Pad87)") (class "Default")
      (node (ref "PCB1") (pin "87") (pinfunction "PO-8_87") (pintype "unspecified+no_connect"))
    )
    (net (code "121") (name "unconnected-(U1-EXTCLK-Pad25)") (class "Default")
      (node (ref "U1") (pin "25") (pinfunction "EXTCLK_25") (pintype "unspecified+no_connect"))
    )
    (net (code "122") (name "unconnected-(U4-EXTCLK-Pad25)") (class "Default")
      (node (ref "U4") (pin "25") (pinfunction "EXTCLK_25") (pintype "unspecified+no_connect"))
    )
  )
)
